# power_supply.net
KiCad netlist of a schematic drawn in Altium Designer
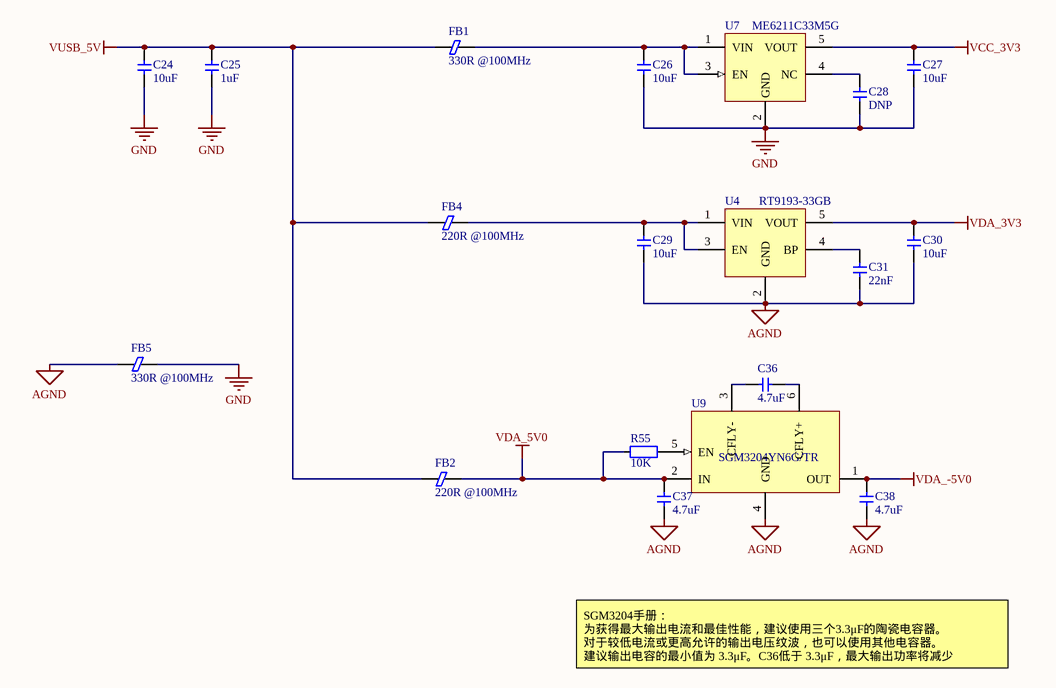
[diagram p0: power_supply.SchDoc]

(export (version "E")
  (design (tool "Eeschema 10.0.6"))
  (components
    (comp (ref "C24")
      (value "10uF")
      (footprint "C0402")
      (description "Capacitor")
      (libsource (lib "ODG_AD_Lib") (part "CAP"))
    )
    (comp (ref "C25")
      (value "1uF")
      (footprint "C0402")
      (description "Capacitor")
      (libsource (lib "ODG_AD_Lib") (part "CAP"))
    )
    (comp (ref "C26")
      (value "10uF")
      (footprint "C0402")
      (description "Capacitor")
      (libsource (lib "ODG_AD_Lib") (part "CAP"))
    )
    (comp (ref "C27")
      (value "10uF")
      (footprint "C0402")
      (description "Capacitor")
      (libsource (lib "ODG_AD_Lib") (part "CAP"))
    )
    (comp (ref "C28")
      (value "DNP")
      (footprint "C0402")
      (description "Capacitor")
      (libsource (lib "ODG_AD_Lib") (part "CAP"))
    )
    (comp (ref "C29")
      (value "10uF")
      (footprint "C0402")
      (description "Capacitor")
      (libsource (lib "ODG_AD_Lib") (part "CAP"))
    )
    (comp (ref "C30")
      (value "10uF")
      (footprint "C0402")
      (description "Capacitor")
      (libsource (lib "ODG_AD_Lib") (part "CAP"))
    )
    (comp (ref "C31")
      (value "22nF")
      (footprint "C0402")
      (description "Capacitor")
      (libsource (lib "ODG_AD_Lib") (part "CAP"))
    )
    (comp (ref "C36")
      (value "4.7uF")
      (footprint "C0402")
      (description "Capacitor")
      (libsource (lib "ODG_AD_Lib") (part "CAP"))
    )
    (comp (ref "C37")
      (value "4.7uF")
      (footprint "C0402")
      (description "Capacitor")
      (libsource (lib "ODG_AD_Lib") (part "CAP"))
    )
    (comp (ref "C38")
      (value "4.7uF")
      (footprint "C0402")
      (description "Capacitor")
      (libsource (lib "ODG_AD_Lib") (part "CAP"))
    )
    (comp (ref "FB1")
      (value "330R @100MHz")
      (footprint "FER0603")
      (description "磁珠")
      (libsource (lib "ODG_AD_Lib") (part "Ferrite"))
    )
    (comp (ref "FB2")
      (value "220R @100MHz")
      (footprint "FER0402")
      (description "磁珠")
      (libsource (lib "ODG_AD_Lib") (part "Ferrite"))
    )
    (comp (ref "FB4")
      (value "220R @100MHz")
      (footprint "FER0402")
      (description "磁珠")
      (libsource (lib "ODG_AD_Lib") (part "Ferrite"))
    )
    (comp (ref "FB5")
      (value "330R @100MHz")
      (footprint "FER0603")
      (description "磁珠")
      (libsource (lib "ODG_AD_Lib") (part "Ferrite"))
    )
    (comp (ref "R55")
      (value "10K")
      (footprint "R0402")
      (description "Resistor")
      (libsource (lib "ODG_AD_Lib") (part "RES"))
    )
    (comp (ref "U4")
      (value "RT9193-33GB")
      (footprint "MICROCHIP SOT-23-5 OT")
      (description "LDO")
      (libsource (lib "ODG_AD_Lib") (part "LP2992"))
    )
    (comp (ref "U7")
      (value "ME6211C33M5G")
      (footprint "ANALOG TSOT-23-5 UJ-5")
      (description "线性稳压芯片")
      (fields (field (name "版权归属") "源创客"))
      (libsource (lib "ODG_AD_Lib") (part "ME6211C33M5G"))
    )
    (comp (ref "U9")
      (value "SGM3204YN6G/TR")
      (footprint "MICROCHIP SOT-23-6 M6")
      (description "Unregulated 200mA\r\nCharge Pump Voltage Inverter \r\n1.4-5.5V to -1.4-5.5V")
      (fields (field (name "版权归属") "源创客"))
      (libsource (lib "ODG_AD_Lib") (part "SGM3204YN6G/TR"))
    )
  )
  (nets
    (net (code "1") (name "AGND") (class "Default")
      (node (ref "C29") (pin "2") (pinfunction "2_2") (pintype "passive"))
      (node (ref "C30") (pin "2") (pinfunction "2_2") (pintype "passive"))
      (node (ref "C31") (pin "2") (pinfunction "2_2") (pintype "passive"))
      (node (ref "C37") (pin "2") (pinfunction "2_2") (pintype "passive"))
      (node (ref "C38") (pin "2") (pinfunction "2_2") (pintype "passive"))
      (node (ref "FB5") (pin "2") (pinfunction "2_2") (pintype "passive"))
      (node (ref "U4") (pin "2") (pinfunction "GND_2") (pintype "passive"))
      (node (ref "U9") (pin "4") (pinfunction "GND_4") (pintype "passive"))
    )
    (net (code "2") (name "GND") (class "Default")
      (node (ref "C24") (pin "2") (pinfunction "2_2") (pintype "passive"))
      (node (ref "C25") (pin "2") (pinfunction "2_2") (pintype "passive"))
      (node (ref "C26") (pin "2") (pinfunction "2_2") (pintype "passive"))
      (node (ref "C27") (pin "2") (pinfunction "2_2") (pintype "passive"))
      (node (ref "C28") (pin "2") (pinfunction "2_2") (pintype "passive"))
      (node (ref "FB5") (pin "1") (pinfunction "1_1") (pintype "passive"))
      (node (ref "U7") (pin "2") (pinfunction "GND_2") (pintype "passive"))
    )
    (net (code "3") (name "Net-(U4-BP)") (class "Default")
      (node (ref "C31") (pin "1") (pinfunction "1_1") (pintype "passive"))
      (node (ref "U4") (pin "4") (pinfunction "BP_4") (pintype "passive"))
    )
    (net (code "4") (name "Net-(U4-EN)") (class "Default")
      (node (ref "C29") (pin "1") (pinfunction "1_1") (pintype "passive"))
      (node (ref "FB4") (pin "2") (pinfunction "2_2") (pintype "passive"))
      (node (ref "U4") (pin "1") (pinfunction "VIN_1") (pintype "passive"))
      (node (ref "U4") (pin "3") (pinfunction "EN_3") (pintype "passive"))
    )
    (net (code "5") (name "Net-(U7-EN)") (class "Default")
      (node (ref "C26") (pin "1") (pinfunction "1_1") (pintype "passive"))
      (node (ref "FB1") (pin "2") (pinfunction "2_2") (pintype "passive"))
      (node (ref "U7") (pin "1") (pinfunction "VIN_1") (pintype "passive"))
      (node (ref "U7") (pin "3") (pinfunction "EN_3") (pintype "input"))
    )
    (net (code "6") (name "Net-(U7-NC)") (class "Default")
      (node (ref "C28") (pin "1") (pinfunction "1_1") (pintype "passive"))
      (node (ref "U7") (pin "4") (pinfunction "NC_4") (pintype "passive"))
    )
    (net (code "7") (name "Net-(U9-CFLY+)") (class "Default")
      (node (ref "C36") (pin "2") (pinfunction "2_2") (pintype "passive"))
      (node (ref "U9") (pin "6") (pinfunction "CFLY+_6") (pintype "passive"))
    )
    (net (code "8") (name "Net-(U9-CFLY-)") (class "Default")
      (node (ref "C36") (pin "1") (pinfunction "1_1") (pintype "passive"))
      (node (ref "U9") (pin "3") (pinfunction "CFLY-_3") (pintype "passive"))
    )
    (net (code "9") (name "Net-(U9-EN)") (class "Default")
      (node (ref "R55") (pin "1") (pinfunction "1_1") (pintype "passive"))
      (node (ref "U9") (pin "5") (pinfunction "EN_5") (pintype "input"))
    )
    (net (code "10") (name "VCC_3V3") (class "Default")
      (node (ref "C27") (pin "1") (pinfunction "1_1") (pintype "passive"))
      (node (ref "U7") (pin "5") (pinfunction "VOUT_5") (pintype "passive"))
    )
    (net (code "11") (name "VDA_-5V0") (class "Default")
      (node (ref "C38") (pin "1") (pinfunction "1_1") (pintype "passive"))
      (node (ref "U9") (pin "1") (pinfunction "OUT_1") (pintype "passive"))
    )
    (net (code "12") (name "VDA_3V3") (class "Default")
      (node (ref "C30") (pin "1") (pinfunction "1_1") (pintype "passive"))
      (node (ref "U4") (pin "5") (pinfunction "VOUT_5") (pintype "passive"))
    )
    (net (code "13") (name "VDA_5V0") (class "Default")
      (node (ref "C37") (pin "1") (pinfunction "1_1") (pintype "passive"))
      (node (ref "FB2") (pin "1") (pinfunction "1_1") (pintype "passive"))
      (node (ref "R55") (pin "2") (pinfunction "2_2") (pintype "passive"))
      (node (ref "U9") (pin "2") (pinfunction "IN_2") (pintype "passive"))
    )
    (net (code "14") (name "VUSB_5V") (class "Default")
      (node (ref "C24") (pin "1") (pinfunction "1_1") (pintype "passive"))
      (node (ref "C25") (pin "1") (pinfunction "1_1") (pintype "passive"))
      (node (ref "FB1") (pin "1") (pinfunction "1_1") (pintype "passive"))
      (node (ref "FB2") (pin "2") (pinfunction "2_2") (pintype "passive"))
      (node (ref "FB4") (pin "1") (pinfunction "1_1") (pintype "passive"))
    )
  )
)
